# Mech_Interface_Port_Deployable.net
KiCad netlist of a schematic drawn in Altium Designer
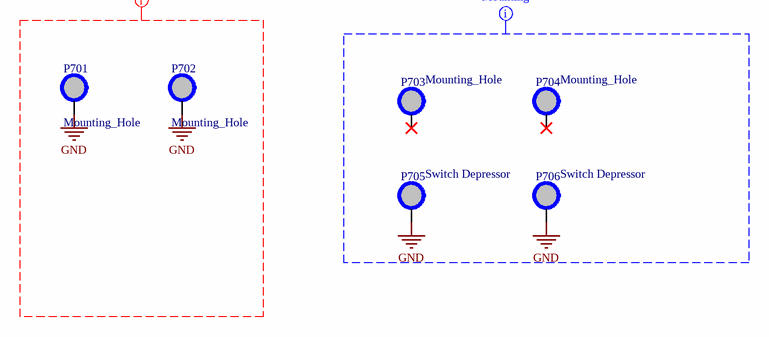
[diagram p0: Mech_Interface_Port_Deployable.SchDoc]

(export (version "E")
  (design (tool "Eeschema 10.0.6"))
  (components
    (comp (ref "P701")
      (value "Mounting_Hole")
      (footprint "Burnwire_Screw_Small_Foot")
      (fields
        (field (name "PART NUMBER") "PXX-ABS-00016")
        (field (name "MANUFACTURER PART NUMBER") "Custom")
        (field (name "PUBLISHER") "AlbertaSat")
      )
      (libsource (lib "Database") (part "Mounting_Hole"))
    )
    (comp (ref "P702")
      (value "Mounting_Hole")
      (footprint "Burnwire_Screw_Small_Foot")
      (fields
        (field (name "PART NUMBER") "PXX-ABS-00016")
        (field (name "MANUFACTURER PART NUMBER") "Custom")
        (field (name "PUBLISHER") "AlbertaSat")
      )
      (libsource (lib "Database") (part "Mounting_Hole"))
    )
    (comp (ref "P703")
      (value "Mounting_Hole")
      (footprint "DepHinge_Mounting_Hole")
      (description "Depolyable Hinge Mounting hole.")
      (fields (field (name "PART NUMBER") "PXX-ABS-00003") (field (name "PUBLISHER") "AlbertaSat"))
      (libsource (lib "Database") (part "Mounting_Hole"))
    )
    (comp (ref "P704")
      (value "Mounting_Hole")
      (footprint "DepHinge_Mounting_Hole")
      (description "Depolyable Hinge Mounting hole.")
      (fields (field (name "PART NUMBER") "PXX-ABS-00003") (field (name "PUBLISHER") "AlbertaSat"))
      (libsource (lib "Database") (part "Mounting_Hole"))
    )
    (comp (ref "P705")
      (value "Switch Depressor")
      (footprint "Switch_Depressor")
      (description "Hardware for depressing the switch")
      (fields
        (field (name "PART NUMBER") "PXX-ABS-00005")
        (field (name "MANUFACTURER PART NUMBER") "Custom")
        (field (name "PUBLISHER") "AlbertaSat")
      )
      (libsource (lib "Database") (part "Mounting_Hole"))
    )
    (comp (ref "P706")
      (value "Switch Depressor")
      (footprint "Switch_Depressor")
      (description "Hardware for depressing the switch")
      (fields
        (field (name "PART NUMBER") "PXX-ABS-00005")
        (field (name "MANUFACTURER PART NUMBER") "Custom")
        (field (name "PUBLISHER") "AlbertaSat")
      )
      (libsource (lib "Database") (part "Mounting_Hole"))
    )
  )
  (nets
    (net (code "1") (name "GND") (class "Default")
      (node (ref "P701") (pin "1") (pinfunction "0_1") (pintype "passive"))
      (node (ref "P702") (pin "1") (pinfunction "0_1") (pintype "passive"))
      (node (ref "P705") (pin "1") (pinfunction "0_1") (pintype "passive"))
      (node (ref "P706") (pin "1") (pinfunction "0_1") (pintype "passive"))
    )
    (net (code "2") (name "unconnected-(P703-0-Pad1)") (class "Default")
      (node (ref "P703") (pin "1") (pinfunction "0_1") (pintype "passive+no_connect"))
    )
    (net (code "3") (name "unconnected-(P704-0-Pad1)") (class "Default")
      (node (ref "P704") (pin "1") (pinfunction "0_1") (pintype "passive+no_connect"))
    )
  )
)
